# HACK_IO-C.net
KiCad netlist of a schematic drawn in Altium Designer
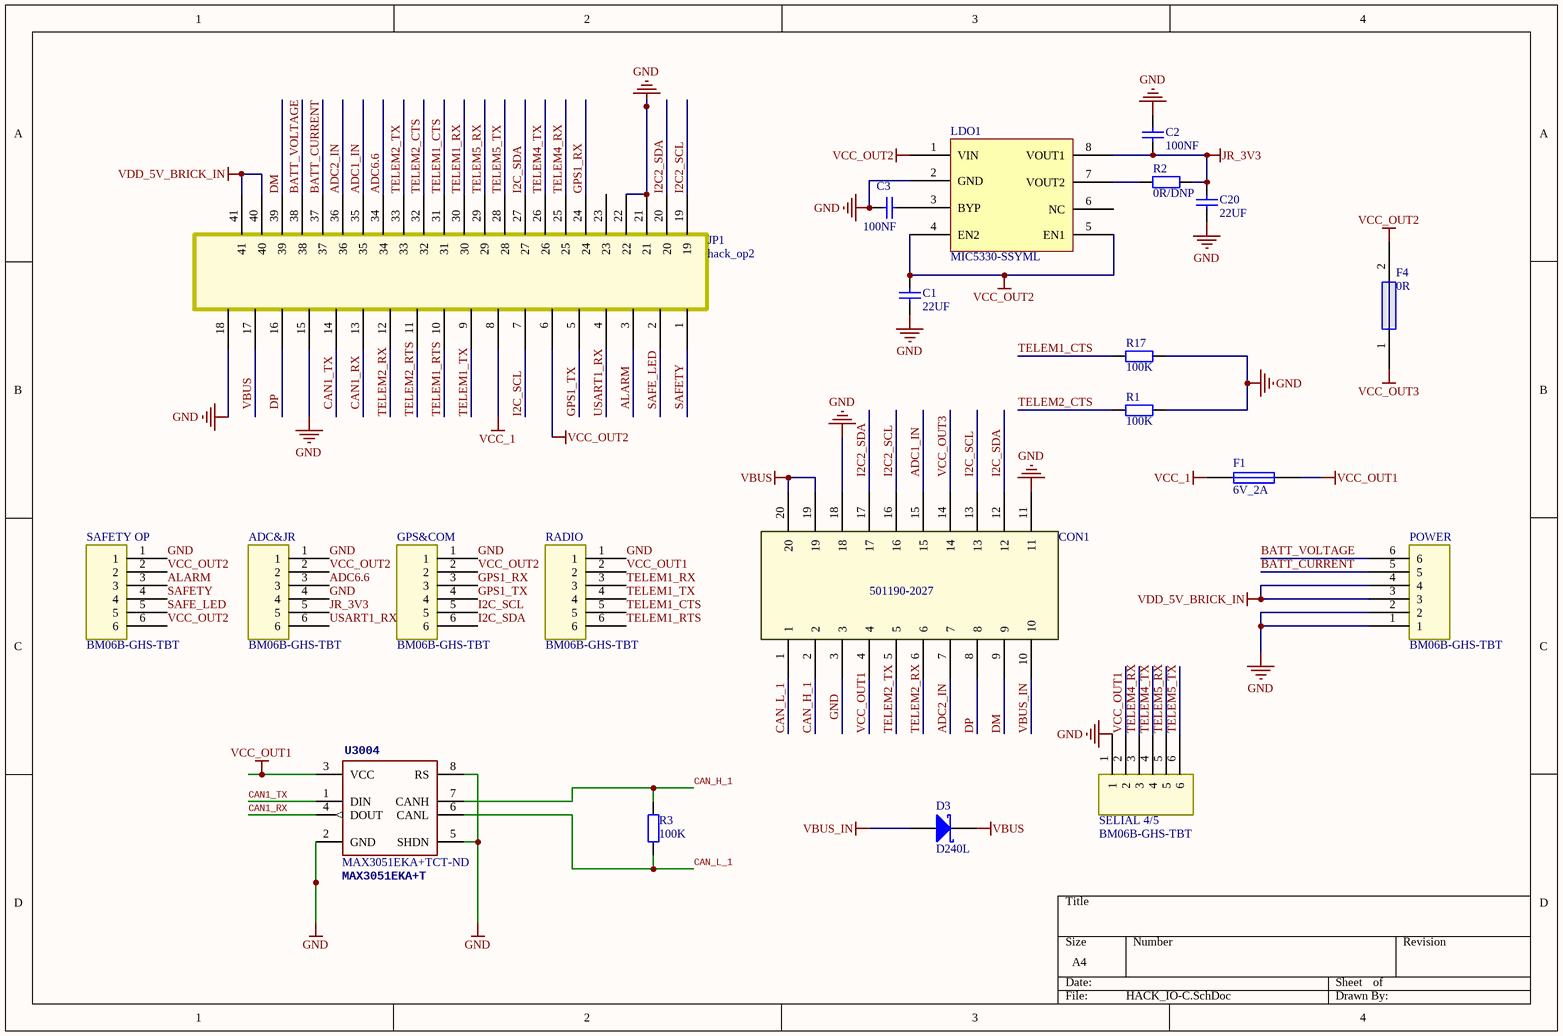
[diagram p0: HACK_IO-C.SchDoc]

(export (version "E")
  (design (tool "Eeschema 10.0.6"))
  (components
    (comp (ref "ADC&JR")
      (value "BM06B-GHS-TBT")
      (footprint "GH1.25-6")
      (libsource (lib "hack") (part "GH1.25-6"))
    )
    (comp (ref "C1")
      (value "22UF")
      (fields (field (name "PUBLISHER") "Altium Limited"))
      (libsource (lib "Miscellaneous Devices") (part "Cap"))
    )
    (comp (ref "C2")
      (value "100NF")
      (fields (field (name "PUBLISHER") "Altium Limited"))
      (libsource (lib "Miscellaneous Devices") (part "Cap"))
    )
    (comp (ref "C3")
      (value "100NF")
      (fields (field (name "PUBLISHER") "Altium Limited"))
      (libsource (lib "Miscellaneous Devices") (part "Cap"))
    )
    (comp (ref "C20")
      (value "22UF")
      (fields (field (name "PUBLISHER") "Altium Limited"))
      (libsource (lib "Miscellaneous Devices") (part "Cap"))
    )
    (comp (ref "CON1") (value "501190-2027") (footprint "SHD1X20") (libsource (lib "hack") (part "SHD1X20")))
    (comp (ref "D3")
      (value "D240L")
      (footprint "SOD-123")
      (description "Schottky Diode")
      (fields (field (name "PUBLISHER") "Altium Limited"))
      (libsource (lib "Miscellaneous Devices") (part "D Schottky"))
    )
    (comp (ref "F1")
      (value "6V_2A")
      (footprint "1206fuse")
      (description "Fuse")
      (fields (field (name "PUBLISHER") "Altium Limited"))
      (libsource (lib "Miscellaneous Devices") (part "Fuse 1"))
    )
    (comp (ref "F4")
      (value "0R")
      (footprint "KYOCERA-KNH16-DA")
      (libsource (lib "hack") (part "KYOCERA-KNH16-DA"))
    )
    (comp (ref "GPS&COM")
      (value "BM06B-GHS-TBT")
      (footprint "GH1.25-6")
      (libsource (lib "hack") (part "GH1.25-6"))
    )
    (comp (ref "JP1") (value "hack_op2") (footprint "hack_op2") (libsource (lib "hack") (part "hack_op2")))
    (comp (ref "LDO1")
      (value "MIC5330-SSYML")
      (footprint "MIC5530")
      (libsource (lib "hack") (part "MIC5530"))
    )
    (comp (ref "POWER")
      (value "BM06B-GHS-TBT")
      (footprint "GH1.25-6")
      (libsource (lib "") (part "GH1.25-6_1"))
    )
    (comp (ref "R1")
      (value "100K")
      (description "Resistor")
      (fields (field (name "PUBLISHER") "Altium Limited"))
      (libsource (lib "Miscellaneous Devices") (part "Res2"))
    )
    (comp (ref "R2")
      (value "0R/DNP")
      (description "Resistor")
      (fields (field (name "PUBLISHER") "Altium Limited"))
      (libsource (lib "") (part "Res2_2"))
    )
    (comp (ref "R3")
      (value "100K")
      (description "Resistor")
      (fields (field (name "PUBLISHER") "Altium Limited"))
      (libsource (lib "") (part "Res2_1"))
    )
    (comp (ref "R17")
      (value "100K")
      (description "Resistor")
      (fields (field (name "PUBLISHER") "Altium Limited"))
      (libsource (lib "Miscellaneous Devices") (part "Res2"))
    )
    (comp (ref "RADIO")
      (value "BM06B-GHS-TBT")
      (footprint "GH1.25-6")
      (libsource (lib "hack") (part "GH1.25-6"))
    )
    (comp (ref "SAFETY OP")
      (value "BM06B-GHS-TBT")
      (footprint "GH1.25-6")
      (libsource (lib "hack") (part "GH1.25-6"))
    )
    (comp (ref "SELIAL 4/5")
      (value "BM06B-GHS-TBT")
      (footprint "GH1.25-6")
      (libsource (lib "") (part "GH1.25-6_2"))
    )
    (comp (ref "U3004")
      (value "MAX3051EKA+T")
      (footprint "SOT23-8")
      (description "IC TXRX CAN 1MBPS SOT23-8")
      (fields
        (field (name "SUPPLIER PART NUMBER 1") "MAX3051EKA+TCT-ND")
        (field (name "3DR_PARTNO") "ECM0831")
      )
      (libsource (lib "pixhawk2") (part "MAX3051MAX3051EKA"))
    )
  )
  (nets
    (net (code "1") (name "/ADC1_IN") (class "Default")
      (node (ref "CON1") (pin "15") (pinfunction "15_15") (pintype "passive"))
      (node (ref "JP1") (pin "35") (pinfunction "35_35") (pintype "passive"))
    )
    (net (code "2") (name "/ADC2_IN") (class "Default")
      (node (ref "CON1") (pin "7") (pinfunction "7_7") (pintype "passive"))
      (node (ref "JP1") (pin "36") (pinfunction "36_36") (pintype "passive"))
    )
    (net (code "3") (name "/ADC6.6") (class "Default")
      (node (ref "ADC&JR") (pin "3") (pinfunction "3_3") (pintype "passive"))
      (node (ref "JP1") (pin "34") (pinfunction "34_34") (pintype "passive"))
    )
    (net (code "4") (name "/ALARM") (class "Default")
      (node (ref "JP1") (pin "3") (pintype "passive"))
      (node (ref "SAFETY OP") (pin "3") (pinfunction "3_3") (pintype "passive"))
    )
    (net (code "5") (name "/BATT_CURRENT") (class "Default")
      (node (ref "JP1") (pin "37") (pinfunction "37_37") (pintype "passive"))
      (node (ref "POWER") (pin "5") (pinfunction "5_5") (pintype "passive"))
    )
    (net (code "6") (name "/BATT_VOLTAGE") (class "Default")
      (node (ref "JP1") (pin "38") (pinfunction "38_38") (pintype "passive"))
      (node (ref "POWER") (pin "6") (pinfunction "6_6") (pintype "passive"))
    )
    (net (code "7") (name "/CAN1_RX") (class "Default")
      (node (ref "JP1") (pin "13") (pintype "passive"))
      (node (ref "U3004") (pin "4") (pinfunction "DOUT_4") (pintype "output"))
    )
    (net (code "8") (name "/CAN1_TX") (class "Default")
      (node (ref "JP1") (pin "14") (pintype "passive"))
      (node (ref "U3004") (pin "1") (pinfunction "DIN_1") (pintype "passive"))
    )
    (net (code "9") (name "/CAN_H_1") (class "Default")
      (node (ref "CON1") (pin "2") (pinfunction "2_2") (pintype "passive"))
      (node (ref "R3") (pin "1") (pinfunction "1_1") (pintype "passive"))
      (node (ref "U3004") (pin "7") (pinfunction "CANH_7") (pintype "passive"))
    )
    (net (code "10") (name "/CAN_L_1") (class "Default")
      (node (ref "CON1") (pin "1") (pinfunction "1_1") (pintype "passive"))
      (node (ref "R3") (pin "2") (pinfunction "2_2") (pintype "passive"))
      (node (ref "U3004") (pin "6") (pinfunction "CANL_6") (pintype "passive"))
    )
    (net (code "11") (name "/DM") (class "Default")
      (node (ref "CON1") (pin "9") (pinfunction "9_9") (pintype "passive"))
      (node (ref "JP1") (pin "39") (pinfunction "39_39") (pintype "passive"))
    )
    (net (code "12") (name "/DP") (class "Default")
      (node (ref "CON1") (pin "8") (pinfunction "8_8") (pintype "passive"))
      (node (ref "JP1") (pin "16") (pintype "passive"))
    )
    (net (code "13") (name "/GPS1_RX") (class "Default")
      (node (ref "GPS&COM") (pin "3") (pinfunction "3_3") (pintype "passive"))
      (node (ref "JP1") (pin "24") (pinfunction "24_24") (pintype "passive"))
    )
    (net (code "14") (name "/GPS1_TX") (class "Default")
      (node (ref "GPS&COM") (pin "4") (pinfunction "4_4") (pintype "passive"))
      (node (ref "JP1") (pin "5") (pintype "passive"))
    )
    (net (code "15") (name "/I2C2_SCL") (class "Default")
      (node (ref "CON1") (pin "16") (pinfunction "16_16") (pintype "passive"))
      (node (ref "JP1") (pin "19") (pinfunction "19_19") (pintype "passive"))
    )
    (net (code "16") (name "/I2C2_SDA") (class "Default")
      (node (ref "CON1") (pin "17") (pinfunction "17_17") (pintype "passive"))
      (node (ref "JP1") (pin "20") (pinfunction "20_20") (pintype "passive"))
    )
    (net (code "17") (name "/I2C_SCL") (class "Default")
      (node (ref "CON1") (pin "13") (pinfunction "13_13") (pintype "passive"))
      (node (ref "GPS&COM") (pin "5") (pinfunction "5_5") (pintype "passive"))
      (node (ref "JP1") (pin "7") (pintype "passive"))
    )
    (net (code "18") (name "/I2C_SDA") (class "Default")
      (node (ref "CON1") (pin "12") (pinfunction "12_12") (pintype "passive"))
      (node (ref "GPS&COM") (pin "6") (pinfunction "6_6") (pintype "passive"))
      (node (ref "JP1") (pin "27") (pinfunction "27_27") (pintype "passive"))
    )
    (net (code "19") (name "/SAFETY") (class "Default")
      (node (ref "JP1") (pin "1") (pintype "passive"))
      (node (ref "SAFETY OP") (pin "4") (pinfunction "4_4") (pintype "passive"))
    )
    (net (code "20") (name "/SAFE_LED") (class "Default")
      (node (ref "JP1") (pin "2") (pintype "passive"))
      (node (ref "SAFETY OP") (pin "5") (pinfunction "5_5") (pintype "passive"))
    )
    (net (code "21") (name "/TELEM1_CTS") (class "Default")
      (node (ref "JP1") (pin "31") (pinfunction "31_31") (pintype "passive"))
      (node (ref "R17") (pin "2") (pinfunction "2_2") (pintype "passive"))
      (node (ref "RADIO") (pin "5") (pinfunction "5_5") (pintype "passive"))
    )
    (net (code "22") (name "/TELEM1_RTS") (class "Default")
      (node (ref "JP1") (pin "10") (pintype "passive"))
      (node (ref "RADIO") (pin "6") (pinfunction "6_6") (pintype "passive"))
    )
    (net (code "23") (name "/TELEM1_RX") (class "Default")
      (node (ref "JP1") (pin "30") (pinfunction "30_30") (pintype "passive"))
      (node (ref "RADIO") (pin "3") (pinfunction "3_3") (pintype "passive"))
    )
    (net (code "24") (name "/TELEM1_TX") (class "Default")
      (node (ref "JP1") (pin "9") (pintype "passive"))
      (node (ref "RADIO") (pin "4") (pinfunction "4_4") (pintype "passive"))
    )
    (net (code "25") (name "/TELEM2_CTS") (class "Default")
      (node (ref "JP1") (pin "32") (pinfunction "32_32") (pintype "passive"))
      (node (ref "R1") (pin "2") (pinfunction "2_2") (pintype "passive"))
    )
    (net (code "26") (name "/TELEM2_RTS") (class "Default") (node (ref "JP1") (pin "11") (pintype "passive")))
    (net (code "27") (name "/TELEM2_RX") (class "Default")
      (node (ref "CON1") (pin "6") (pinfunction "6_6") (pintype "passive"))
      (node (ref "JP1") (pin "12") (pintype "passive"))
    )
    (net (code "28") (name "/TELEM2_TX") (class "Default")
      (node (ref "CON1") (pin "5") (pinfunction "5_5") (pintype "passive"))
      (node (ref "JP1") (pin "33") (pinfunction "33_33") (pintype "passive"))
    )
    (net (code "29") (name "/TELEM4_RX") (class "Default")
      (node (ref "JP1") (pin "25") (pinfunction "25_25") (pintype "passive"))
      (node (ref "SELIAL 4/5") (pin "3") (pinfunction "3_3") (pintype "passive"))
    )
    (net (code "30") (name "/TELEM4_TX") (class "Default")
      (node (ref "JP1") (pin "26") (pinfunction "26_26") (pintype "passive"))
      (node (ref "SELIAL 4/5") (pin "4") (pinfunction "4_4") (pintype "passive"))
    )
    (net (code "31") (name "/TELEM5_RX") (class "Default")
      (node (ref "JP1") (pin "29") (pinfunction "29_29") (pintype "passive"))
      (node (ref "SELIAL 4/5") (pin "5") (pinfunction "5_5") (pintype "passive"))
    )
    (net (code "32") (name "/TELEM5_TX") (class "Default")
      (node (ref "JP1") (pin "28") (pinfunction "28_28") (pintype "passive"))
      (node (ref "SELIAL 4/5") (pin "6") (pinfunction "6_6") (pintype "passive"))
    )
    (net (code "33") (name "/USART1_RX") (class "Default")
      (node (ref "ADC&JR") (pin "6") (pinfunction "6_6") (pintype "passive"))
      (node (ref "JP1") (pin "4") (pintype "passive"))
    )
    (net (code "34") (name "GND") (class "Default")
      (node (ref "ADC&JR") (pin "1") (pinfunction "1_1") (pintype "passive"))
      (node (ref "ADC&JR") (pin "4") (pinfunction "4_4") (pintype "passive"))
      (node (ref "C1") (pin "1") (pinfunction "1_1") (pintype "passive"))
      (node (ref "C2") (pin "1") (pinfunction "1_1") (pintype "passive"))
      (node (ref "C20") (pin "2") (pinfunction "2_2") (pintype "passive"))
      (node (ref "C3") (pin "2") (pinfunction "2_2") (pintype "passive"))
      (node (ref "CON1") (pin "11") (pinfunction "11_11") (pintype "passive"))
      (node (ref "CON1") (pin "18") (pinfunction "18_18") (pintype "passive"))
      (node (ref "CON1") (pin "3") (pinfunction "3_3") (pintype "passive"))
      (node (ref "GPS&COM") (pin "1") (pinfunction "1_1") (pintype "passive"))
      (node (ref "JP1") (pin "15") (pintype "passive"))
      (node (ref "JP1") (pin "18") (pintype "passive"))
      (node (ref "JP1") (pin "21") (pinfunction "21_21") (pintype "passive"))
      (node (ref "JP1") (pin "22") (pinfunction "22_22") (pintype "passive"))
      (node (ref "LDO1") (pin "2") (pinfunction "GND_2") (pintype "passive"))
      (node (ref "POWER") (pin "1") (pinfunction "1_1") (pintype "passive"))
      (node (ref "POWER") (pin "2") (pinfunction "2_2") (pintype "passive"))
      (node (ref "R1") (pin "1") (pinfunction "1_1") (pintype "passive"))
      (node (ref "R17") (pin "1") (pinfunction "1_1") (pintype "passive"))
      (node (ref "RADIO") (pin "1") (pinfunction "1_1") (pintype "passive"))
      (node (ref "SAFETY OP") (pin "1") (pinfunction "1_1") (pintype "passive"))
      (node (ref "SELIAL 4/5") (pin "1") (pinfunction "1_1") (pintype "passive"))
      (node (ref "U3004") (pin "2") (pinfunction "GND_2") (pintype "open_emitter"))
      (node (ref "U3004") (pin "5") (pinfunction "SHDN_5") (pintype "passive"))
      (node (ref "U3004") (pin "8") (pinfunction "RS_8") (pintype "passive"))
    )
    (net (code "35") (name "JR_3V3") (class "Default")
      (node (ref "ADC&JR") (pin "5") (pinfunction "5_5") (pintype "passive"))
      (node (ref "C2") (pin "2") (pinfunction "2_2") (pintype "passive"))
      (node (ref "C20") (pin "1") (pinfunction "1_1") (pintype "passive"))
      (node (ref "LDO1") (pin "8") (pinfunction "VOUT1_8") (pintype "passive"))
      (node (ref "R2") (pin "2") (pinfunction "2_2") (pintype "passive"))
    )
    (net (code "36") (name "Net-(LDO1-BYP)") (class "Default")
      (node (ref "C3") (pin "1") (pinfunction "1_1") (pintype "passive"))
      (node (ref "LDO1") (pin "3") (pinfunction "BYP_3") (pintype "passive"))
    )
    (net (code "37") (name "Net-(LDO1-VOUT2)") (class "Default")
      (node (ref "LDO1") (pin "7") (pinfunction "VOUT2_7") (pintype "passive"))
      (node (ref "R2") (pin "1") (pinfunction "1_1") (pintype "passive"))
    )
    (net (code "38") (name "VBUS") (class "Default")
      (node (ref "CON1") (pin "19") (pinfunction "19_19") (pintype "passive"))
      (node (ref "CON1") (pin "20") (pinfunction "20_20") (pintype "passive"))
      (node (ref "D3") (pin "2") (pinfunction "K_2") (pintype "passive"))
      (node (ref "JP1") (pin "17") (pintype "passive"))
    )
    (net (code "39") (name "VBUS_IN") (class "Default")
      (node (ref "CON1") (pin "10") (pinfunction "10_10") (pintype "passive"))
      (node (ref "D3") (pin "1") (pinfunction "A_1") (pintype "passive"))
    )
    (net (code "40") (name "VCC_1") (class "Default")
      (node (ref "F1") (pin "2") (pinfunction "2_2") (pintype "passive"))
      (node (ref "JP1") (pin "8") (pintype "passive"))
    )
    (net (code "41") (name "VCC_OUT1") (class "Default")
      (node (ref "CON1") (pin "4") (pinfunction "4_4") (pintype "passive"))
      (node (ref "F1") (pin "1") (pinfunction "1_1") (pintype "passive"))
      (node (ref "RADIO") (pin "2") (pinfunction "2_2") (pintype "passive"))
      (node (ref "SELIAL 4/5") (pin "2") (pinfunction "2_2") (pintype "passive"))
      (node (ref "U3004") (pin "3") (pinfunction "VCC_3") (pintype "passive"))
    )
    (net (code "42") (name "VCC_OUT2") (class "Default")
      (node (ref "ADC&JR") (pin "2") (pinfunction "2_2") (pintype "passive"))
      (node (ref "C1") (pin "2") (pinfunction "2_2") (pintype "passive"))
      (node (ref "F4") (pin "2") (pinfunction "2_2") (pintype "passive"))
      (node (ref "GPS&COM") (pin "2") (pinfunction "2_2") (pintype "passive"))
      (node (ref "JP1") (pin "6") (pintype "passive"))
      (node (ref "LDO1") (pin "1") (pinfunction "VIN_1") (pintype "passive"))
      (node (ref "LDO1") (pin "4") (pinfunction "EN2_4") (pintype "passive"))
      (node (ref "LDO1") (pin "5") (pinfunction "EN1_5") (pintype "passive"))
      (node (ref "SAFETY OP") (pin "2") (pinfunction "2_2") (pintype "passive"))
      (node (ref "SAFETY OP") (pin "6") (pinfunction "6_6") (pintype "passive"))
    )
    (net (code "43") (name "VCC_OUT3") (class "Default")
      (node (ref "CON1") (pin "14") (pinfunction "14_14") (pintype "passive"))
      (node (ref "F4") (pin "1") (pinfunction "1_1") (pintype "passive"))
    )
    (net (code "44") (name "VDD_5V_BRICK_IN") (class "Default")
      (node (ref "JP1") (pin "40") (pinfunction "40_40") (pintype "passive"))
      (node (ref "JP1") (pin "41") (pinfunction "41_41") (pintype "passive"))
      (node (ref "POWER") (pin "3") (pinfunction "3_3") (pintype "passive"))
      (node (ref "POWER") (pin "4") (pinfunction "4_4") (pintype "passive"))
    )
    (net (code "45") (name "unconnected-(JP1-Pad23)") (class "Default")
      (node (ref "JP1") (pin "23") (pinfunction "23_23") (pintype "passive"))
    )
    (net (code "46") (name "unconnected-(LDO1-NC-Pad6)") (class "Default")
      (node (ref "LDO1") (pin "6") (pinfunction "NC_6") (pintype "passive"))
    )
  )
)
